# mdriver.net
KiCad netlist of a schematic drawn in Altium Designer
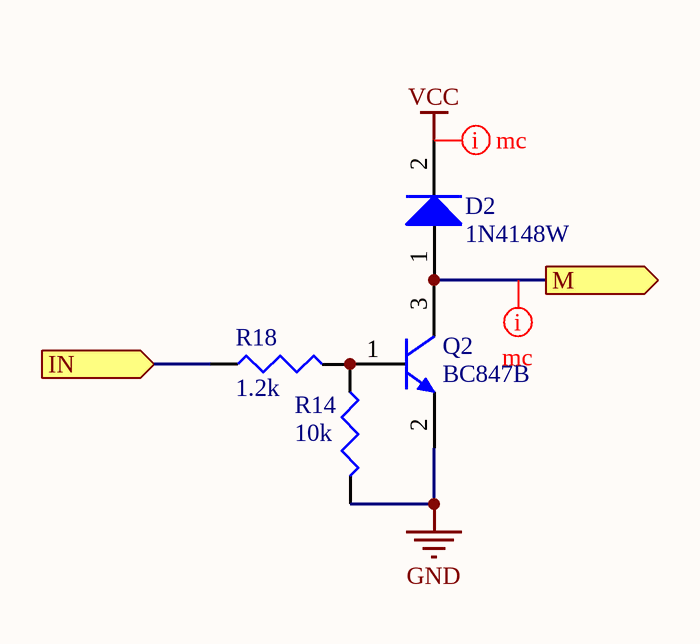
[diagram p0: mdriver.SchDoc]

(export (version "E")
  (design (tool "Eeschema 10.0.6"))
  (components
    (comp (ref "D2")
      (value "1N4148W")
      (footprint "SOD-123")
      (description "Default Diode")
      (fields (field (name "PUBLISHER") "Altium Limited"))
      (libsource (lib "Miscellaneous Devices") (part "Diode"))
    )
    (comp (ref "Q2")
      (value "BC847B")
      (footprint "SOT-23_N")
      (description "NPN Bipolar Transistor")
      (fields (field (name "PUBLISHER") "Altium Limited"))
      (libsource (lib "Miscellaneous Devices") (part "NPN"))
    )
    (comp (ref "R14")
      (value "10k")
      (footprint "J1-0603")
      (description "Resistor")
      (fields (field (name "PUBLISHER") "Altium Limited"))
      (libsource (lib "Miscellaneous Devices") (part "Res3"))
    )
    (comp (ref "R18")
      (value "1.2k")
      (footprint "J1-0603")
      (description "Resistor")
      (fields (field (name "PUBLISHER") "Altium Limited"))
      (libsource (lib "Miscellaneous Devices") (part "Res3"))
    )
  )
  (nets
    (net (code "1") (name "/IN") (class "Default")
      (node (ref "R18") (pin "1") (pinfunction "1_1") (pintype "passive"))
    )
    (net (code "2") (name "/M") (class "Default")
      (node (ref "D2") (pin "1") (pinfunction "A_1") (pintype "passive"))
      (node (ref "Q2") (pin "3") (pinfunction "C_3") (pintype "passive"))
    )
    (net (code "3") (name "GND") (class "Default")
      (node (ref "Q2") (pin "2") (pinfunction "E_2") (pintype "passive"))
      (node (ref "R14") (pin "2") (pinfunction "2_2") (pintype "passive"))
    )
    (net (code "4") (name "Net-(Q2-B)") (class "Default")
      (node (ref "Q2") (pin "1") (pinfunction "B_1") (pintype "passive"))
      (node (ref "R14") (pin "1") (pinfunction "1_1") (pintype "passive"))
      (node (ref "R18") (pin "2") (pinfunction "2_2") (pintype "passive"))
    )
    (net (code "5") (name "VCC") (class "Default")
      (node (ref "D2") (pin "2") (pinfunction "K_2") (pintype "passive"))
    )
  )
)
